# rotary_encoder_ver1.net
KiCad netlist of a schematic drawn in EAGLE
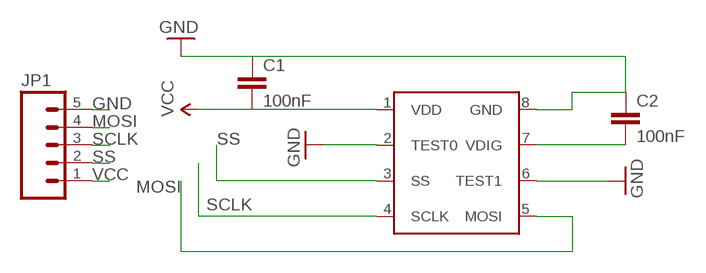
[diagram p0: schematic, sheet 1]

(export (version "E")
  (design (tool "Eeschema 10.0.6"))
  (components
    (comp (ref "C1")
      (value "100nF")
      (footprint "eagle-import:1206")
      (libsource (lib "eagle-import") (part "CAP1206"))
    )
    (comp (ref "C2")
      (value "100nF")
      (footprint "eagle-import:1206")
      (libsource (lib "eagle-import") (part "CAP1206"))
    )
    (comp (ref "JP1")
      (value "M05PTH")
      (footprint "eagle-import:1X05")
      (libsource (lib "eagle-import") (part "M05PTH"))
    )
    (comp (ref "U$1")
      (value "MLX90316")
      (footprint "eagle-import:8-SOIC_MLX90316")
      (libsource (lib "eagle-import") (part "MLX90316"))
    )
  )
  (nets
    (net (code "1") (name "/MOSI") (class "Default")
      (node (ref "JP1") (pin "4") (pinfunction "4_4") (pintype "passive"))
      (node (ref "U$1") (pin "5") (pinfunction "MOSI_5") (pintype "bidirectional"))
    )
    (net (code "2") (name "/SCLK") (class "Default")
      (node (ref "JP1") (pin "3") (pinfunction "3_3") (pintype "passive"))
      (node (ref "U$1") (pin "4") (pinfunction "SCLK_4") (pintype "bidirectional"))
    )
    (net (code "3") (name "/SS") (class "Default")
      (node (ref "JP1") (pin "2") (pinfunction "2_2") (pintype "passive"))
      (node (ref "U$1") (pin "3") (pinfunction "SS_3") (pintype "bidirectional"))
    )
    (net (code "4") (name "GND") (class "Default")
      (node (ref "C1") (pin "1") (pinfunction "1_1") (pintype "passive"))
      (node (ref "C2") (pin "1") (pinfunction "1_1") (pintype "passive"))
      (node (ref "JP1") (pin "5") (pinfunction "5_5") (pintype "passive"))
      (node (ref "U$1") (pin "2") (pinfunction "TEST0_2") (pintype "bidirectional"))
      (node (ref "U$1") (pin "6") (pinfunction "TEST1_6") (pintype "bidirectional"))
      (node (ref "U$1") (pin "8") (pinfunction "GND_8") (pintype "bidirectional"))
    )
    (net (code "5") (name "Net-(U$1-VDIG)") (class "Default")
      (node (ref "C2") (pin "2") (pinfunction "2_2") (pintype "passive"))
      (node (ref "U$1") (pin "7") (pinfunction "VDIG_7") (pintype "bidirectional"))
    )
    (net (code "6") (name "VCC") (class "Default")
      (node (ref "C1") (pin "2") (pinfunction "2_2") (pintype "passive"))
      (node (ref "JP1") (pin "1") (pinfunction "1_1") (pintype "passive"))
      (node (ref "U$1") (pin "1") (pinfunction "VDD_1") (pintype "bidirectional"))
    )
  )
)
